# V1_0.net
KiCad netlist of a schematic drawn in Altium Designer
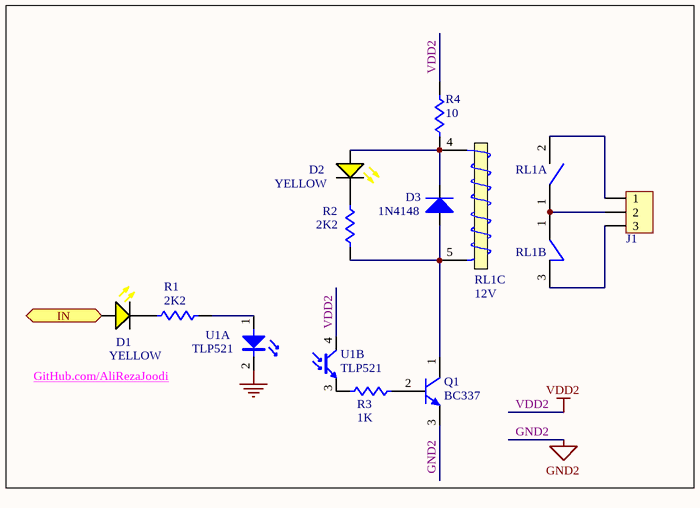
[diagram p0: V1.0.SchDoc]

(export (version "E")
  (design (tool "Eeschema 10.0.6"))
  (components
    (comp (ref "D1")
      (value "YELLOW")
      (footprint "LED_THD_5MM_YELLOW")
      (description "LED, Yellow")
      (fields (field (name "MANUFACTURER") "Generic Components") (field (name "PUBLISHER") "Altium Limited"))
      (libsource (lib "Display") (part "LED_YELLOW"))
    )
    (comp (ref "D2")
      (value "YELLOW")
      (footprint "LED_THD_5MM_YELLOW")
      (description "LED, Yellow")
      (fields (field (name "MANUFACTURER") "Generic Components") (field (name "PUBLISHER") "Altium Limited"))
      (libsource (lib "Display") (part "LED_YELLOW"))
    )
    (comp (ref "D3")
      (value "1N4148")
      (footprint "DIODE0.4_Glass")
      (description "Default Diode")
      (fields (field (name "MANUFACTURER") "Generic Components") (field (name "PUBLISHER") "Altium Limited"))
      (libsource (lib "Miscellaneous Devices") (part "Diode"))
    )
    (comp (ref "J1")
      (value "3PIN")
      (description "Connector, Header, 3Pin")
      (libsource (lib "Connector") (part "Connector_Header_3Pin"))
    )
    (comp (ref "Q1")
      (value "BC337")
      (footprint "TO92C")
      (description "NPN Bipolar Transistor")
      (fields (field (name "MANUFACTURER") "Generic Components") (field (name "PUBLISHER") "Altium Limited"))
      (libsource (lib "Miscellaneous Devices") (part "NPN"))
    )
    (comp (ref "R1")
      (value "2K2")
      (footprint "AXIAL-0.4")
      (description "Resistor")
      (fields (field (name "MANUFACTURER") "Generic Components") (field (name "PUBLISHER") "Altium Limited"))
      (libsource (lib "Miscellaneous Devices") (part "Res1"))
    )
    (comp (ref "R2")
      (value "2K2")
      (footprint "AXIAL-0.4")
      (description "Resistor")
      (fields (field (name "MANUFACTURER") "Generic Components") (field (name "PUBLISHER") "Altium Limited"))
      (libsource (lib "Miscellaneous Devices") (part "Res1"))
    )
    (comp (ref "R3")
      (value "1K")
      (footprint "AXIAL-0.4")
      (description "Resistor")
      (fields (field (name "MANUFACTURER") "Generic Components") (field (name "PUBLISHER") "Altium Limited"))
      (libsource (lib "Miscellaneous Devices") (part "Res1"))
    )
    (comp (ref "R4")
      (value "10")
      (footprint "AXIAL-0.4")
      (description "Resistor")
      (fields (field (name "MANUFACTURER") "Generic Components") (field (name "PUBLISHER") "Altium Limited"))
      (libsource (lib "Miscellaneous Devices") (part "Res1"))
    )
    (comp (ref "RL1")
      (value "12V")
      (footprint "RELAY-SPDT-1")
      (description "SPDT Relay")
      (fields (field (name "MANUFACTURER") "Generic Components") (field (name "PUBLISHER") "Altium Limited"))
      (libsource (lib "Other_Myself") (part "Relay_SPDT_3"))
    )
    (comp (ref "U1")
      (value "TLP521")
      (footprint "DIP_4")
      (description "Optoisolator")
      (fields (field (name "PUBLISHER") "Altium Limited"))
      (libsource (lib "Other_Myself") (part "Optoisolator"))
    )
  )
  (nets
    (net (code "1") (name "/IN") (class "Default")
      (node (ref "D1") (pin "1") (pinfunction "A_1") (pintype "passive"))
    )
    (net (code "2") (name "GND") (class "Default")
      (node (ref "U1") (pin "2") (pinfunction "K_2") (pintype "power_in"))
    )
    (net (code "3") (name "GND2") (class "Default")
      (node (ref "Q1") (pin "3") (pinfunction "E_3") (pintype "passive"))
    )
    (net (code "4") (name "Net-(D1-K)") (class "Default")
      (node (ref "D1") (pin "2") (pinfunction "K_2") (pintype "passive"))
      (node (ref "R1") (pin "2") (pinfunction "2_2") (pintype "passive"))
    )
    (net (code "5") (name "Net-(D2-A)") (class "Default")
      (node (ref "D2") (pin "1") (pinfunction "A_1") (pintype "passive"))
      (node (ref "D3") (pin "2") (pinfunction "K_2") (pintype "passive"))
      (node (ref "R4") (pin "2") (pinfunction "2_2") (pintype "passive"))
      (node (ref "RL1") (pin "4") (pinfunction "T1_4") (pintype "passive"))
    )
    (net (code "6") (name "Net-(D2-K)") (class "Default")
      (node (ref "D2") (pin "2") (pinfunction "K_2") (pintype "passive"))
      (node (ref "R2") (pin "1") (pinfunction "1_1") (pintype "passive"))
    )
    (net (code "7") (name "Net-(D3-A)") (class "Default")
      (node (ref "D3") (pin "1") (pinfunction "A_1") (pintype "passive"))
      (node (ref "Q1") (pin "1") (pinfunction "C_1") (pintype "passive"))
      (node (ref "R2") (pin "2") (pinfunction "2_2") (pintype "passive"))
      (node (ref "RL1") (pin "5") (pinfunction "T2_5") (pintype "passive"))
    )
    (net (code "8") (name "Net-(Q1-B)") (class "Default")
      (node (ref "Q1") (pin "2") (pinfunction "B_2") (pintype "passive"))
      (node (ref "R3") (pin "1") (pinfunction "1_1") (pintype "passive"))
    )
    (net (code "9") (name "Net-(RL1A-COM)") (class "Default")
      (node (ref "J1") (pin "2") (pinfunction "2_2") (pintype "passive"))
      (node (ref "RL1") (pin "1") (pinfunction "COM_1") (pintype "passive"))
    )
    (net (code "10") (name "Net-(RL1A-NC)") (class "Default")
      (node (ref "J1") (pin "1") (pinfunction "1_1") (pintype "passive"))
      (node (ref "RL1") (pin "2") (pinfunction "NC_2") (pintype "passive"))
    )
    (net (code "11") (name "Net-(RL1B-NC)") (class "Default")
      (node (ref "J1") (pin "3") (pinfunction "3_3") (pintype "passive"))
      (node (ref "RL1") (pin "3") (pinfunction "NC_3") (pintype "passive"))
    )
    (net (code "12") (name "Net-(U1A-A)") (class "Default")
      (node (ref "R1") (pin "1") (pinfunction "1_1") (pintype "passive"))
      (node (ref "U1") (pin "1") (pinfunction "A_1") (pintype "power_in"))
    )
    (net (code "13") (name "Net-(U1B-E)") (class "Default")
      (node (ref "R3") (pin "2") (pinfunction "2_2") (pintype "passive"))
      (node (ref "U1") (pin "3") (pinfunction "E_3") (pintype "passive"))
    )
    (net (code "14") (name "VDD2") (class "Default")
      (node (ref "R4") (pin "1") (pinfunction "1_1") (pintype "passive"))
      (node (ref "U1") (pin "4") (pinfunction "C_4") (pintype "passive"))
    )
  )
)
